# siedle-switch.net
KiCad netlist of a schematic drawn in EAGLE
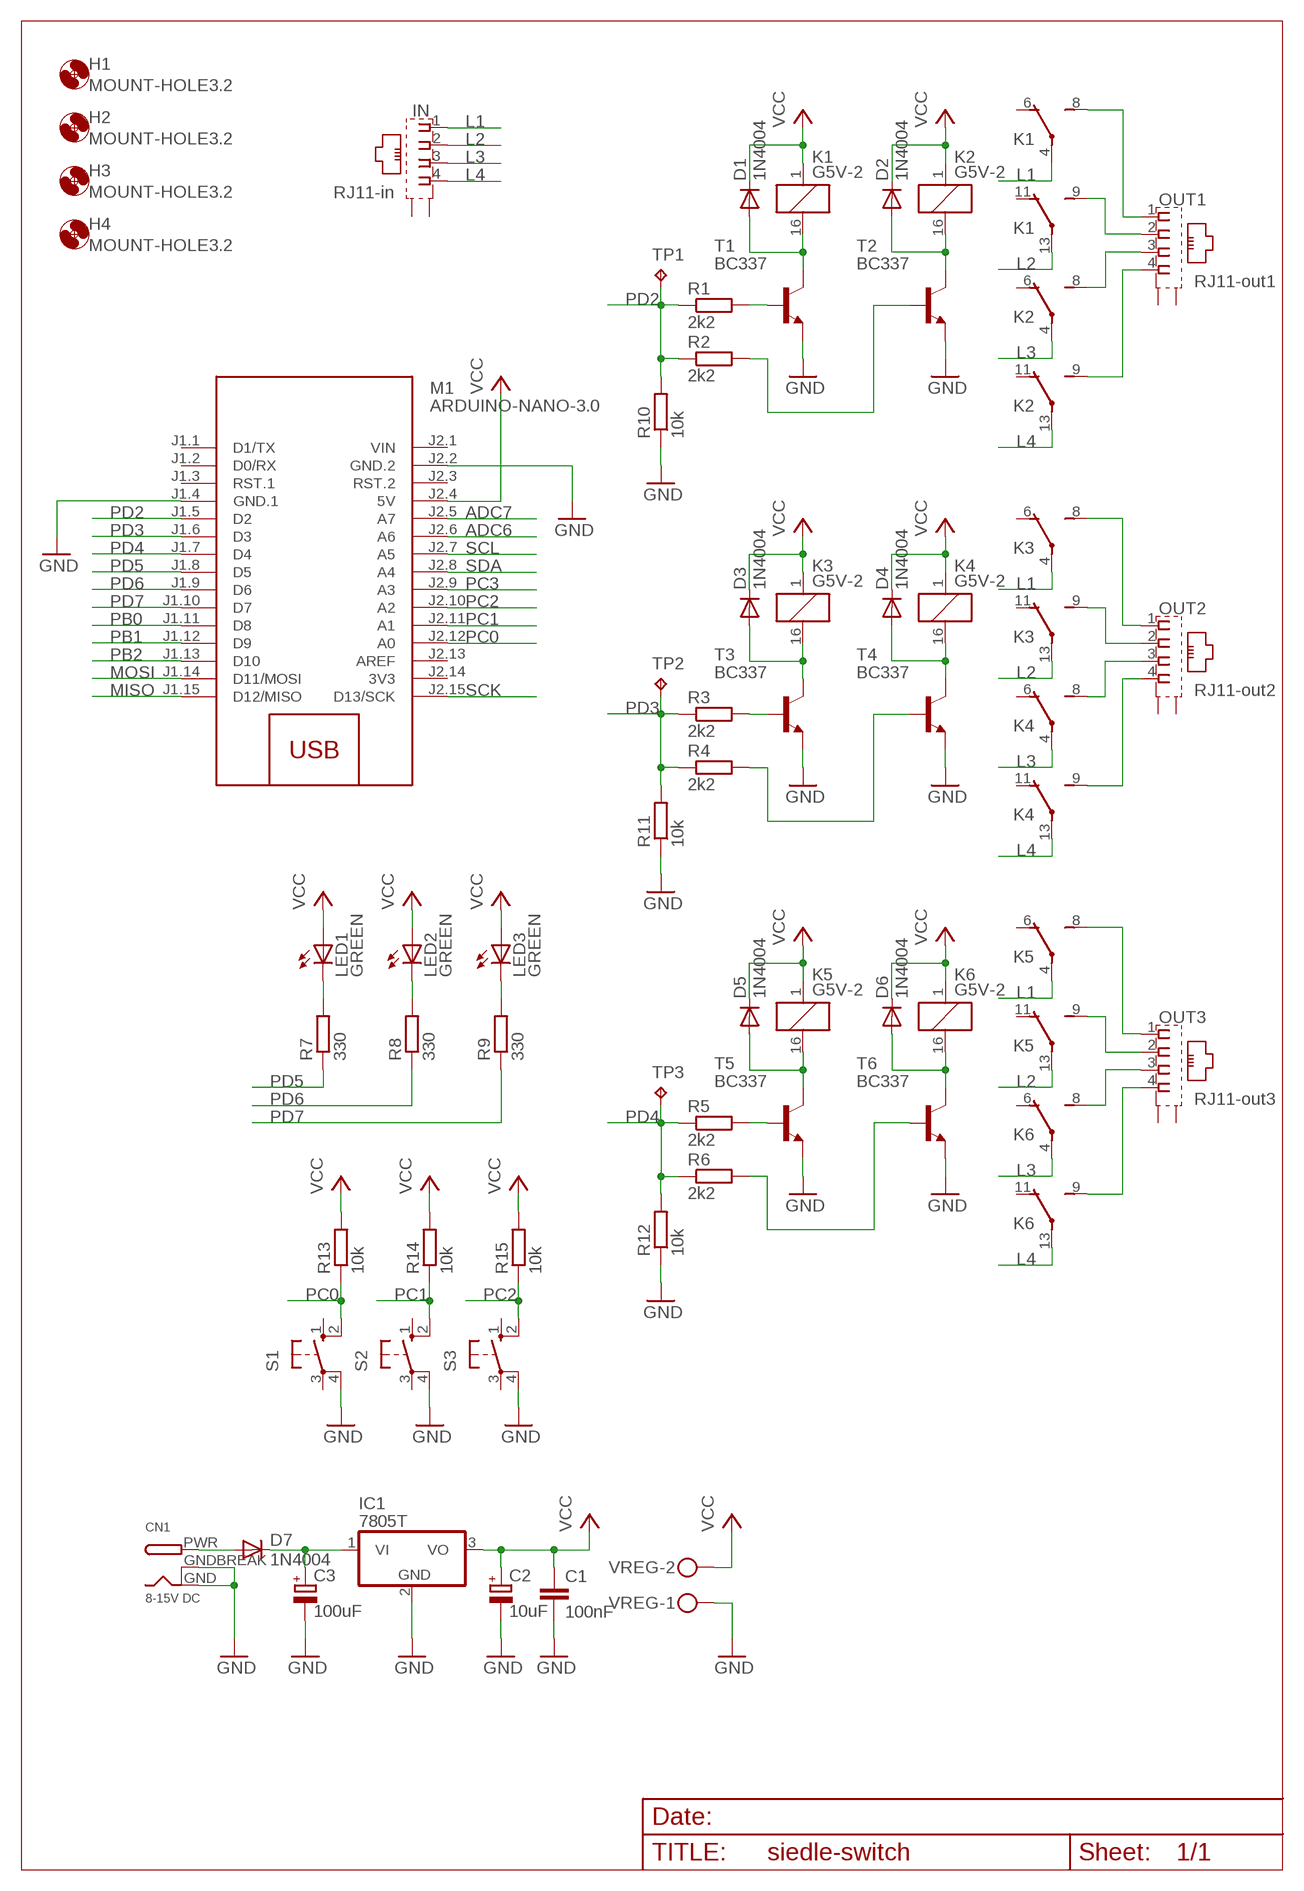
[diagram p0: schematic, sheet 1]

(export (version "E")
  (design (tool "Eeschema 10.0.6"))
  (components
    (comp (ref "C1")
      (value "100nF")
      (footprint "eagle-import:C1206")
      (libsource (lib "eagle-import") (part "C-EUC1206"))
    )
    (comp (ref "C2")
      (value "10uF")
      (footprint "eagle-import:E2,5-5")
      (libsource (lib "eagle-import") (part "CPOL-EUE2.5-5"))
    )
    (comp (ref "C3")
      (value "100uF")
      (footprint "eagle-import:E3,5-8")
      (libsource (lib "eagle-import") (part "CPOL-EUE3.5-8"))
    )
    (comp (ref "CN1")
      (value "8-15V DC")
      (footprint "eagle-import:DCJACK_2MM_PTH")
      (libsource (lib "eagle-import") (part "DCBARRELPTH"))
    )
    (comp (ref "D1")
      (value "1N4004")
      (footprint "eagle-import:DO41-10")
      (libsource (lib "eagle-import") (part "1N4004"))
    )
    (comp (ref "D2")
      (value "1N4004")
      (footprint "eagle-import:DO41-10")
      (libsource (lib "eagle-import") (part "1N4004"))
    )
    (comp (ref "D3")
      (value "1N4004")
      (footprint "eagle-import:DO41-10")
      (libsource (lib "eagle-import") (part "1N4004"))
    )
    (comp (ref "D4")
      (value "1N4004")
      (footprint "eagle-import:DO41-10")
      (libsource (lib "eagle-import") (part "1N4004"))
    )
    (comp (ref "D5")
      (value "1N4004")
      (footprint "eagle-import:DO41-10")
      (libsource (lib "eagle-import") (part "1N4004"))
    )
    (comp (ref "D6")
      (value "1N4004")
      (footprint "eagle-import:DO41-10")
      (libsource (lib "eagle-import") (part "1N4004"))
    )
    (comp (ref "D7")
      (value "1N4004")
      (footprint "eagle-import:DO41-10")
      (libsource (lib "eagle-import") (part "1N4004"))
    )
    (comp (ref "H1")
      (value "MOUNT-HOLE3.2")
      (footprint "eagle-import:3,2")
      (libsource (lib "eagle-import") (part "MOUNT-HOLE3.2"))
    )
    (comp (ref "H2")
      (value "MOUNT-HOLE3.2")
      (footprint "eagle-import:3,2")
      (libsource (lib "eagle-import") (part "MOUNT-HOLE3.2"))
    )
    (comp (ref "H3")
      (value "MOUNT-HOLE3.2")
      (footprint "eagle-import:3,2")
      (libsource (lib "eagle-import") (part "MOUNT-HOLE3.2"))
    )
    (comp (ref "H4")
      (value "MOUNT-HOLE3.2")
      (footprint "eagle-import:3,2")
      (libsource (lib "eagle-import") (part "MOUNT-HOLE3.2"))
    )
    (comp (ref "IC1")
      (value "7805T")
      (footprint "eagle-import:TO220H")
      (libsource (lib "eagle-import") (part "78T05"))
    )
    (comp (ref "IN")
      (value "RJ11-in")
      (footprint "eagle-import:XRJK-S-01-6-4-0-9M2")
      (libsource (lib "eagle-import") (part "XRJK4-0-9M2-S-01-6-"))
    )
    (comp (ref "K1")
      (value "G5V-2")
      (footprint "eagle-import:G5V-2")
      (fields (field (name "MPN") "G5V-2 5DC"))
      (libsource (lib "eagle-import") (part "G5V-2"))
    )
    (comp (ref "K2")
      (value "G5V-2")
      (footprint "eagle-import:G5V-2")
      (fields (field (name "MPN") "G5V-2 5DC"))
      (libsource (lib "eagle-import") (part "G5V-2"))
    )
    (comp (ref "K3")
      (value "G5V-2")
      (footprint "eagle-import:G5V-2")
      (fields (field (name "MPN") "G5V-2 5DC"))
      (libsource (lib "eagle-import") (part "G5V-2"))
    )
    (comp (ref "K4")
      (value "G5V-2")
      (footprint "eagle-import:G5V-2")
      (fields (field (name "MPN") "G5V-2 5DC"))
      (libsource (lib "eagle-import") (part "G5V-2"))
    )
    (comp (ref "K5")
      (value "G5V-2")
      (footprint "eagle-import:G5V-2")
      (fields (field (name "MPN") "G5V-2 5DC"))
      (libsource (lib "eagle-import") (part "G5V-2"))
    )
    (comp (ref "K6")
      (value "G5V-2")
      (footprint "eagle-import:G5V-2")
      (fields (field (name "MPN") "G5V-2 5DC"))
      (libsource (lib "eagle-import") (part "G5V-2"))
    )
    (comp (ref "LED1")
      (value "GREEN")
      (footprint "eagle-import:LED3MM")
      (libsource (lib "eagle-import") (part "LED3MM"))
    )
    (comp (ref "LED2")
      (value "GREEN")
      (footprint "eagle-import:LED3MM")
      (libsource (lib "eagle-import") (part "LED3MM"))
    )
    (comp (ref "LED3")
      (value "GREEN")
      (footprint "eagle-import:LED3MM")
      (libsource (lib "eagle-import") (part "LED3MM"))
    )
    (comp (ref "M1")
      (value "ARDUINO-NANO-3.0")
      (footprint "eagle-import:ARDUINO-NANO-3.0")
      (libsource (lib "eagle-import") (part "ARDUINO-NANO-3.0"))
    )
    (comp (ref "OUT1")
      (value "RJ11-out1")
      (footprint "eagle-import:XRJK-S-01-6-4-0-9M2")
      (libsource (lib "eagle-import") (part "XRJK4-0-9M2-S-01-6-"))
    )
    (comp (ref "OUT2")
      (value "RJ11-out2")
      (footprint "eagle-import:XRJK-S-01-6-4-0-9M2")
      (libsource (lib "eagle-import") (part "XRJK4-0-9M2-S-01-6-"))
    )
    (comp (ref "OUT3")
      (value "RJ11-out3")
      (footprint "eagle-import:XRJK-S-01-6-4-0-9M2")
      (libsource (lib "eagle-import") (part "XRJK4-0-9M2-S-01-6-"))
    )
    (comp (ref "R1")
      (value "2k2")
      (footprint "eagle-import:0309_10")
      (libsource (lib "eagle-import") (part "R-EU_0309/10"))
    )
    (comp (ref "R2")
      (value "2k2")
      (footprint "eagle-import:0309_10")
      (libsource (lib "eagle-import") (part "R-EU_0309/10"))
    )
    (comp (ref "R3")
      (value "2k2")
      (footprint "eagle-import:0309_10")
      (libsource (lib "eagle-import") (part "R-EU_0309/10"))
    )
    (comp (ref "R4")
      (value "2k2")
      (footprint "eagle-import:0309_10")
      (libsource (lib "eagle-import") (part "R-EU_0309/10"))
    )
    (comp (ref "R5")
      (value "2k2")
      (footprint "eagle-import:0309_10")
      (libsource (lib "eagle-import") (part "R-EU_0309/10"))
    )
    (comp (ref "R6")
      (value "2k2")
      (footprint "eagle-import:0309_10")
      (libsource (lib "eagle-import") (part "R-EU_0309/10"))
    )
    (comp (ref "R7")
      (value "330")
      (footprint "eagle-import:0309_10")
      (libsource (lib "eagle-import") (part "R-EU_0309/10"))
    )
    (comp (ref "R8")
      (value "330")
      (footprint "eagle-import:0309_10")
      (libsource (lib "eagle-import") (part "R-EU_0309/10"))
    )
    (comp (ref "R9")
      (value "330")
      (footprint "eagle-import:0309_10")
      (libsource (lib "eagle-import") (part "R-EU_0309/10"))
    )
    (comp (ref "R10")
      (value "10k")
      (footprint "eagle-import:0309_10")
      (libsource (lib "eagle-import") (part "R-EU_0309/10"))
    )
    (comp (ref "R11")
      (value "10k")
      (footprint "eagle-import:0309_10")
      (libsource (lib "eagle-import") (part "R-EU_0309/10"))
    )
    (comp (ref "R12")
      (value "10k")
      (footprint "eagle-import:0309_10")
      (libsource (lib "eagle-import") (part "R-EU_0309/10"))
    )
    (comp (ref "R13")
      (value "10k")
      (footprint "eagle-import:0309_10")
      (libsource (lib "eagle-import") (part "R-EU_0309/10"))
    )
    (comp (ref "R14")
      (value "10k")
      (footprint "eagle-import:0309_10")
      (libsource (lib "eagle-import") (part "R-EU_0309/10"))
    )
    (comp (ref "R15")
      (value "10k")
      (footprint "eagle-import:0309_10")
      (libsource (lib "eagle-import") (part "R-EU_0309/10"))
    )
    (comp (ref "S1")
      (value "10-XX")
      (footprint "eagle-import:B3F-10XX")
      (fields (field (name "MPN") "B3F-1000"))
      (libsource (lib "eagle-import") (part "10-XX"))
    )
    (comp (ref "S2")
      (value "10-XX")
      (footprint "eagle-import:B3F-10XX")
      (fields (field (name "MPN") "B3F-1000"))
      (libsource (lib "eagle-import") (part "10-XX"))
    )
    (comp (ref "S3")
      (value "10-XX")
      (footprint "eagle-import:B3F-10XX")
      (fields (field (name "MPN") "B3F-1000"))
      (libsource (lib "eagle-import") (part "10-XX"))
    )
    (comp (ref "T1")
      (value "BC337")
      (footprint "eagle-import:TO92")
      (libsource (lib "eagle-import") (part "BC337"))
    )
    (comp (ref "T2")
      (value "BC337")
      (footprint "eagle-import:TO92")
      (libsource (lib "eagle-import") (part "BC337"))
    )
    (comp (ref "T3")
      (value "BC337")
      (footprint "eagle-import:TO92")
      (libsource (lib "eagle-import") (part "BC337"))
    )
    (comp (ref "T4")
      (value "BC337")
      (footprint "eagle-import:TO92")
      (libsource (lib "eagle-import") (part "BC337"))
    )
    (comp (ref "T5")
      (value "BC337")
      (footprint "eagle-import:TO92")
      (libsource (lib "eagle-import") (part "BC337"))
    )
    (comp (ref "T6")
      (value "BC337")
      (footprint "eagle-import:TO92")
      (libsource (lib "eagle-import") (part "BC337"))
    )
    (comp (ref "TP1")
      (value "TPPAD1-13")
      (footprint "eagle-import:P1-13")
      (libsource (lib "eagle-import") (part "TPPAD1-13"))
    )
    (comp (ref "TP2")
      (value "TPPAD1-13")
      (footprint "eagle-import:P1-13")
      (libsource (lib "eagle-import") (part "TPPAD1-13"))
    )
    (comp (ref "TP3")
      (value "TPPAD1-13")
      (footprint "eagle-import:P1-13")
      (libsource (lib "eagle-import") (part "TPPAD1-13"))
    )
    (comp (ref "VREG")
      (value "MKDSN1,5/2-5,08")
      (footprint "eagle-import:MKDSN1,5_2-5,08")
      (fields (field (name "MPN") "MKDSN 1,5/2-5.08"))
      (libsource (lib "eagle-import") (part "MKDSN1,5/2-5,08"))
    )
  )
  (nets
    (net (code "1") (name "/3V3") (class "Default")
      (node (ref "M1") (pin "J2.14") (pinfunction "3V3_J2.14") (pintype "power_in"))
    )
    (net (code "2") (name "/ADC6") (class "Default")
      (node (ref "M1") (pin "J2.6") (pinfunction "A6_J2.6") (pintype "bidirectional"))
    )
    (net (code "3") (name "/ADC7") (class "Default")
      (node (ref "M1") (pin "J2.5") (pinfunction "A7_J2.5") (pintype "bidirectional"))
    )
    (net (code "4") (name "/L1") (class "Default")
      (node (ref "IN") (pin "1") (pinfunction "1_1") (pintype "passive"))
      (node (ref "K1") (pin "4") (pinfunction "P_4") (pintype "passive"))
      (node (ref "K3") (pin "4") (pinfunction "P_4") (pintype "passive"))
      (node (ref "K5") (pin "4") (pinfunction "P_4") (pintype "passive"))
    )
    (net (code "5") (name "/L2") (class "Default")
      (node (ref "IN") (pin "2") (pinfunction "2_2") (pintype "passive"))
      (node (ref "K1") (pin "13") (pinfunction "P_13") (pintype "passive"))
      (node (ref "K3") (pin "13") (pinfunction "P_13") (pintype "passive"))
      (node (ref "K5") (pin "13") (pinfunction "P_13") (pintype "passive"))
    )
    (net (code "6") (name "/L3") (class "Default")
      (node (ref "IN") (pin "3") (pinfunction "3_3") (pintype "passive"))
      (node (ref "K2") (pin "4") (pinfunction "P_4") (pintype "passive"))
      (node (ref "K4") (pin "4") (pinfunction "P_4") (pintype "passive"))
      (node (ref "K6") (pin "4") (pinfunction "P_4") (pintype "passive"))
    )
    (net (code "7") (name "/L4") (class "Default")
      (node (ref "IN") (pin "4") (pinfunction "4_4") (pintype "passive"))
      (node (ref "K2") (pin "13") (pinfunction "P_13") (pintype "passive"))
      (node (ref "K4") (pin "13") (pinfunction "P_13") (pintype "passive"))
      (node (ref "K6") (pin "13") (pinfunction "P_13") (pintype "passive"))
    )
    (net (code "8") (name "/MISO") (class "Default")
      (node (ref "M1") (pin "J1.15") (pinfunction "D12/MISO_J1.15") (pintype "bidirectional"))
    )
    (net (code "9") (name "/MOSI") (class "Default")
      (node (ref "M1") (pin "J1.14") (pinfunction "D11/MOSI_J1.14") (pintype "bidirectional"))
    )
    (net (code "10") (name "/PB0") (class "Default")
      (node (ref "M1") (pin "J1.11") (pinfunction "D8_J1.11") (pintype "bidirectional"))
    )
    (net (code "11") (name "/PB1") (class "Default")
      (node (ref "M1") (pin "J1.12") (pinfunction "D9_J1.12") (pintype "bidirectional"))
    )
    (net (code "12") (name "/PB2") (class "Default")
      (node (ref "M1") (pin "J1.13") (pinfunction "D10_J1.13") (pintype "bidirectional"))
    )
    (net (code "13") (name "/PC0") (class "Default")
      (node (ref "M1") (pin "J2.12") (pinfunction "A0_J2.12") (pintype "bidirectional"))
      (node (ref "R13") (pin "1") (pinfunction "1_1") (pintype "passive"))
      (node (ref "S1") (pin "2") (pinfunction "S1_2") (pintype "passive"))
    )
    (net (code "14") (name "/PC1") (class "Default")
      (node (ref "M1") (pin "J2.11") (pinfunction "A1_J2.11") (pintype "bidirectional"))
      (node (ref "R14") (pin "1") (pinfunction "1_1") (pintype "passive"))
      (node (ref "S2") (pin "2") (pinfunction "S1_2") (pintype "passive"))
    )
    (net (code "15") (name "/PC2") (class "Default")
      (node (ref "M1") (pin "J2.10") (pinfunction "A2_J2.10") (pintype "bidirectional"))
      (node (ref "R15") (pin "1") (pinfunction "1_1") (pintype "passive"))
      (node (ref "S3") (pin "2") (pinfunction "S1_2") (pintype "passive"))
    )
    (net (code "16") (name "/PC3") (class "Default")
      (node (ref "M1") (pin "J2.9") (pinfunction "A3_J2.9") (pintype "bidirectional"))
    )
    (net (code "17") (name "/PD2") (class "Default")
      (node (ref "M1") (pin "J1.5") (pinfunction "D2_J1.5") (pintype "bidirectional"))
      (node (ref "R1") (pin "1") (pinfunction "1_1") (pintype "passive"))
      (node (ref "R10") (pin "2") (pinfunction "2_2") (pintype "passive"))
      (node (ref "R2") (pin "1") (pinfunction "1_1") (pintype "passive"))
      (node (ref "TP1") (pin "TP") (pinfunction "TP_TP") (pintype "input"))
    )
    (net (code "18") (name "/PD3") (class "Default")
      (node (ref "M1") (pin "J1.6") (pinfunction "D3_J1.6") (pintype "bidirectional"))
      (node (ref "R11") (pin "2") (pinfunction "2_2") (pintype "passive"))
      (node (ref "R3") (pin "1") (pinfunction "1_1") (pintype "passive"))
      (node (ref "R4") (pin "1") (pinfunction "1_1") (pintype "passive"))
      (node (ref "TP2") (pin "TP") (pinfunction "TP_TP") (pintype "input"))
    )
    (net (code "19") (name "/PD4") (class "Default")
      (node (ref "M1") (pin "J1.7") (pinfunction "D4_J1.7") (pintype "bidirectional"))
      (node (ref "R12") (pin "2") (pinfunction "2_2") (pintype "passive"))
      (node (ref "R5") (pin "1") (pinfunction "1_1") (pintype "passive"))
      (node (ref "R6") (pin "1") (pinfunction "1_1") (pintype "passive"))
      (node (ref "TP3") (pin "TP") (pinfunction "TP_TP") (pintype "input"))
    )
    (net (code "20") (name "/PD5") (class "Default")
      (node (ref "M1") (pin "J1.8") (pinfunction "D5_J1.8") (pintype "bidirectional"))
      (node (ref "R7") (pin "1") (pinfunction "1_1") (pintype "passive"))
    )
    (net (code "21") (name "/PD6") (class "Default")
      (node (ref "M1") (pin "J1.9") (pinfunction "D6_J1.9") (pintype "bidirectional"))
      (node (ref "R8") (pin "1") (pinfunction "1_1") (pintype "passive"))
    )
    (net (code "22") (name "/PD7") (class "Default")
      (node (ref "M1") (pin "J1.10") (pinfunction "D7_J1.10") (pintype "bidirectional"))
      (node (ref "R9") (pin "1") (pinfunction "1_1") (pintype "passive"))
    )
    (net (code "23") (name "/SCK") (class "Default")
      (node (ref "M1") (pin "J2.15") (pinfunction "D13/SCK_J2.15") (pintype "bidirectional"))
    )
    (net (code "24") (name "/SCL") (class "Default")
      (node (ref "M1") (pin "J2.7") (pinfunction "A5_J2.7") (pintype "bidirectional"))
    )
    (net (code "25") (name "/SDA") (class "Default")
      (node (ref "M1") (pin "J2.8") (pinfunction "A4_J2.8") (pintype "bidirectional"))
    )
    (net (code "26") (name "/VIN") (class "Default")
      (node (ref "M1") (pin "J2.1") (pinfunction "VIN_J2.1") (pintype "power_in"))
    )
    (net (code "27") (name "GND") (class "Default")
      (node (ref "C1") (pin "2") (pinfunction "2_2") (pintype "passive"))
      (node (ref "C2") (pin "-") (pinfunction "-_-") (pintype "passive"))
      (node (ref "C3") (pin "-") (pinfunction "-_-") (pintype "passive"))
      (node (ref "CN1") (pin "GND") (pinfunction "GND_GND") (pintype "power_in"))
      (node (ref "CN1") (pin "GNDBREAK") (pinfunction "GNDBREAK_GNDBREAK") (pintype "power_in"))
      (node (ref "IC1") (pin "2") (pinfunction "GND_2") (pintype "passive"))
      (node (ref "M1") (pin "J1.4") (pinfunction "GND.1_J1.4") (pintype "power_in"))
      (node (ref "M1") (pin "J2.2") (pinfunction "GND.2_J2.2") (pintype "power_in"))
      (node (ref "R10") (pin "1") (pinfunction "1_1") (pintype "passive"))
      (node (ref "R11") (pin "1") (pinfunction "1_1") (pintype "passive"))
      (node (ref "R12") (pin "1") (pinfunction "1_1") (pintype "passive"))
      (node (ref "S1") (pin "4") (pinfunction "P1_4") (pintype "passive"))
      (node (ref "S2") (pin "4") (pinfunction "P1_4") (pintype "passive"))
      (node (ref "S3") (pin "4") (pinfunction "P1_4") (pintype "passive"))
      (node (ref "T1") (pin "1") (pinfunction "E_1") (pintype "passive"))
      (node (ref "T2") (pin "1") (pinfunction "E_1") (pintype "passive"))
      (node (ref "T3") (pin "1") (pinfunction "E_1") (pintype "passive"))
      (node (ref "T4") (pin "1") (pinfunction "E_1") (pintype "passive"))
      (node (ref "T5") (pin "1") (pinfunction "E_1") (pintype "passive"))
      (node (ref "T6") (pin "1") (pinfunction "E_1") (pintype "passive"))
      (node (ref "VREG") (pin "1") (pinfunction "KL_1") (pintype "passive"))
    )
    (net (code "28") (name "Net-(CN1-PadPWR)") (class "Default")
      (node (ref "CN1") (pin "PWR") (pinfunction "PWR_PWR") (pintype "power_in"))
      (node (ref "D7") (pin "A") (pinfunction "A_A") (pintype "passive"))
    )
    (net (code "29") (name "Net-(IC1-VI)") (class "Default")
      (node (ref "C3") (pin "+") (pinfunction "+_+") (pintype "passive"))
      (node (ref "D7") (pin "C") (pinfunction "C_C") (pintype "passive"))
      (node (ref "IC1") (pin "1") (pinfunction "VI_1") (pintype "input"))
    )
    (net (code "30") (name "Net-(K1A-S)") (class "Default")
      (node (ref "K1") (pin "8") (pinfunction "S_8") (pintype "passive"))
      (node (ref "OUT1") (pin "1") (pinfunction "1_1") (pintype "passive"))
    )
    (net (code "31") (name "Net-(K1B-S)") (class "Default")
      (node (ref "K1") (pin "9") (pinfunction "S_9") (pintype "passive"))
      (node (ref "OUT1") (pin "2") (pinfunction "2_2") (pintype "passive"))
    )
    (net (code "32") (name "Net-(K1C-2)") (class "Default")
      (node (ref "D1") (pin "A") (pinfunction "A_A") (pintype "passive"))
      (node (ref "K1") (pin "16") (pinfunction "2_16") (pintype "passive"))
      (node (ref "T1") (pin "3") (pinfunction "C_3") (pintype "passive"))
    )
    (net (code "33") (name "Net-(K2A-S)") (class "Default")
      (node (ref "K2") (pin "8") (pinfunction "S_8") (pintype "passive"))
      (node (ref "OUT1") (pin "3") (pinfunction "3_3") (pintype "passive"))
    )
    (net (code "34") (name "Net-(K2B-S)") (class "Default")
      (node (ref "K2") (pin "9") (pinfunction "S_9") (pintype "passive"))
      (node (ref "OUT1") (pin "4") (pinfunction "4_4") (pintype "passive"))
    )
    (net (code "35") (name "Net-(K2C-2)") (class "Default")
      (node (ref "D2") (pin "A") (pinfunction "A_A") (pintype "passive"))
      (node (ref "K2") (pin "16") (pinfunction "2_16") (pintype "passive"))
      (node (ref "T2") (pin "3") (pinfunction "C_3") (pintype "passive"))
    )
    (net (code "36") (name "Net-(K3A-S)") (class "Default")
      (node (ref "K3") (pin "8") (pinfunction "S_8") (pintype "passive"))
      (node (ref "OUT2") (pin "1") (pinfunction "1_1") (pintype "passive"))
    )
    (net (code "37") (name "Net-(K3B-S)") (class "Default")
      (node (ref "K3") (pin "9") (pinfunction "S_9") (pintype "passive"))
      (node (ref "OUT2") (pin "2") (pinfunction "2_2") (pintype "passive"))
    )
    (net (code "38") (name "Net-(K3C-2)") (class "Default")
      (node (ref "D3") (pin "A") (pinfunction "A_A") (pintype "passive"))
      (node (ref "K3") (pin "16") (pinfunction "2_16") (pintype "passive"))
      (node (ref "T3") (pin "3") (pinfunction "C_3") (pintype "passive"))
    )
    (net (code "39") (name "Net-(K4A-S)") (class "Default")
      (node (ref "K4") (pin "8") (pinfunction "S_8") (pintype "passive"))
      (node (ref "OUT2") (pin "3") (pinfunction "3_3") (pintype "passive"))
    )
    (net (code "40") (name "Net-(K4B-S)") (class "Default")
      (node (ref "K4") (pin "9") (pinfunction "S_9") (pintype "passive"))
      (node (ref "OUT2") (pin "4") (pinfunction "4_4") (pintype "passive"))
    )
    (net (code "41") (name "Net-(K4C-2)") (class "Default")
      (node (ref "D4") (pin "A") (pinfunction "A_A") (pintype "passive"))
      (node (ref "K4") (pin "16") (pinfunction "2_16") (pintype "passive"))
      (node (ref "T4") (pin "3") (pinfunction "C_3") (pintype "passive"))
    )
    (net (code "42") (name "Net-(K5A-S)") (class "Default")
      (node (ref "K5") (pin "8") (pinfunction "S_8") (pintype "passive"))
      (node (ref "OUT3") (pin "1") (pinfunction "1_1") (pintype "passive"))
    )
    (net (code "43") (name "Net-(K5B-S)") (class "Default")
      (node (ref "K5") (pin "9") (pinfunction "S_9") (pintype "passive"))
      (node (ref "OUT3") (pin "2") (pinfunction "2_2") (pintype "passive"))
    )
    (net (code "44") (name "Net-(K5C-2)") (class "Default")
      (node (ref "D5") (pin "A") (pinfunction "A_A") (pintype "passive"))
      (node (ref "K5") (pin "16") (pinfunction "2_16") (pintype "passive"))
      (node (ref "T5") (pin "3") (pinfunction "C_3") (pintype "passive"))
    )
    (net (code "45") (name "Net-(K6A-S)") (class "Default")
      (node (ref "K6") (pin "8") (pinfunction "S_8") (pintype "passive"))
      (node (ref "OUT3") (pin "3") (pinfunction "3_3") (pintype "passive"))
    )
    (net (code "46") (name "Net-(K6B-S)") (class "Default")
      (node (ref "K6") (pin "9") (pinfunction "S_9") (pintype "passive"))
      (node (ref "OUT3") (pin "4") (pinfunction "4_4") (pintype "passive"))
    )
    (net (code "47") (name "Net-(K6C-2)") (class "Default")
      (node (ref "D6") (pin "A") (pinfunction "A_A") (pintype "passive"))
      (node (ref "K6") (pin "16") (pinfunction "2_16") (pintype "passive"))
      (node (ref "T6") (pin "3") (pinfunction "C_3") (pintype "passive"))
    )
    (net (code "48") (name "Net-(LED1-C)") (class "Default")
      (node (ref "LED1") (pin "K") (pinfunction "C_K") (pintype "passive"))
      (node (ref "R7") (pin "2") (pinfunction "2_2") (pintype "passive"))
    )
    (net (code "49") (name "Net-(LED2-C)") (class "Default")
      (node (ref "LED2") (pin "K") (pinfunction "C_K") (pintype "passive"))
      (node (ref "R8") (pin "2") (pinfunction "2_2") (pintype "passive"))
    )
    (net (code "50") (name "Net-(LED3-C)") (class "Default")
      (node (ref "LED3") (pin "K") (pinfunction "C_K") (pintype "passive"))
      (node (ref "R9") (pin "2") (pinfunction "2_2") (pintype "passive"))
    )
    (net (code "51") (name "Net-(T1-B)") (class "Default")
      (node (ref "R1") (pin "2") (pinfunction "2_2") (pintype "passive"))
      (node (ref "T1") (pin "2") (pinfunction "B_2") (pintype "passive"))
    )
    (net (code "52") (name "Net-(T2-B)") (class "Default")
      (node (ref "R2") (pin "2") (pinfunction "2_2") (pintype "passive"))
      (node (ref "T2") (pin "2") (pinfunction "B_2") (pintype "passive"))
    )
    (net (code "53") (name "Net-(T3-B)") (class "Default")
      (node (ref "R3") (pin "2") (pinfunction "2_2") (pintype "passive"))
      (node (ref "T3") (pin "2") (pinfunction "B_2") (pintype "passive"))
    )
    (net (code "54") (name "Net-(T4-B)") (class "Default")
      (node (ref "R4") (pin "2") (pinfunction "2_2") (pintype "passive"))
      (node (ref "T4") (pin "2") (pinfunction "B_2") (pintype "passive"))
    )
    (net (code "55") (name "Net-(T5-B)") (class "Default")
      (node (ref "R5") (pin "2") (pinfunction "2_2") (pintype "passive"))
      (node (ref "T5") (pin "2") (pinfunction "B_2") (pintype "passive"))
    )
    (net (code "56") (name "Net-(T6-B)") (class "Default")
      (node (ref "R6") (pin "2") (pinfunction "2_2") (pintype "passive"))
      (node (ref "T6") (pin "2") (pinfunction "B_2") (pintype "passive"))
    )
    (net (code "57") (name "VCC") (class "Default")
      (node (ref "C1") (pin "1") (pinfunction "1_1") (pintype "passive"))
      (node (ref "C2") (pin "+") (pinfunction "+_+") (pintype "passive"))
      (node (ref "D1") (pin "C") (pinfunction "C_C") (pintype "passive"))
      (node (ref "D2") (pin "C") (pinfunction "C_C") (pintype "passive"))
      (node (ref "D3") (pin "C") (pinfunction "C_C") (pintype "passive"))
      (node (ref "D4") (pin "C") (pinfunction "C_C") (pintype "passive"))
      (node (ref "D5") (pin "C") (pinfunction "C_C") (pintype "passive"))
      (node (ref "D6") (pin "C") (pinfunction "C_C") (pintype "passive"))
      (node (ref "IC1") (pin "3") (pinfunction "VO_3") (pintype "passive"))
      (node (ref "K1") (pin "1") (pinfunction "1_1") (pintype "passive"))
      (node (ref "K2") (pin "1") (pinfunction "1_1") (pintype "passive"))
      (node (ref "K3") (pin "1") (pinfunction "1_1") (pintype "passive"))
      (node (ref "K4") (pin "1") (pinfunction "1_1") (pintype "passive"))
      (node (ref "K5") (pin "1") (pinfunction "1_1") (pintype "passive"))
      (node (ref "K6") (pin "1") (pinfunction "1_1") (pintype "passive"))
      (node (ref "LED1") (pin "A") (pinfunction "A_A") (pintype "passive"))
      (node (ref "LED2") (pin "A") (pinfunction "A_A") (pintype "passive"))
      (node (ref "LED3") (pin "A") (pinfunction "A_A") (pintype "passive"))
      (node (ref "M1") (pin "J2.4") (pinfunction "5V_J2.4") (pintype "power_in"))
      (node (ref "R13") (pin "2") (pinfunction "2_2") (pintype "passive"))
      (node (ref "R14") (pin "2") (pinfunction "2_2") (pintype "passive"))
      (node (ref "R15") (pin "2") (pinfunction "2_2") (pintype "passive"))
      (node (ref "VREG") (pin "2") (pinfunction "KL_2") (pintype "passive"))
    )
    (net (code "58") (name "unconnected-(IN-S-PadS1)") (class "Default")
      (node (ref "IN") (pin "S1") (pinfunction "S_S1") (pintype "passive"))
    )
    (net (code "59") (name "unconnected-(IN-S-PadS2)") (class "Default")
      (node (ref "IN") (pin "S2") (pinfunction "S_S2") (pintype "passive"))
    )
    (net (code "60") (name "unconnected-(K1A-O-Pad6)") (class "Default")
      (node (ref "K1") (pin "6") (pinfunction "O_6") (pintype "passive"))
    )
    (net (code "61") (name "unconnected-(K1B-O-Pad11)") (class "Default")
      (node (ref "K1") (pin "11") (pinfunction "O_11") (pintype "passive"))
    )
    (net (code "62") (name "unconnected-(K2A-O-Pad6)") (class "Default")
      (node (ref "K2") (pin "6") (pinfunction "O_6") (pintype "passive"))
    )
    (net (code "63") (name "unconnected-(K2B-O-Pad11)") (class "Default")
      (node (ref "K2") (pin "11") (pinfunction "O_11") (pintype "passive"))
    )
    (net (code "64") (name "unconnected-(K3A-O-Pad6)") (class "Default")
      (node (ref "K3") (pin "6") (pinfunction "O_6") (pintype "passive"))
    )
    (net (code "65") (name "unconnected-(K3B-O-Pad11)") (class "Default")
      (node (ref "K3") (pin "11") (pinfunction "O_11") (pintype "passive"))
    )
    (net (code "66") (name "unconnected-(K4A-O-Pad6)") (class "Default")
      (node (ref "K4") (pin "6") (pinfunction "O_6") (pintype "passive"))
    )
    (net (code "67") (name "unconnected-(K4B-O-Pad11)") (class "Default")
      (node (ref "K4") (pin "11") (pinfunction "O_11") (pintype "passive"))
    )
    (net (code "68") (name "unconnected-(K5A-O-Pad6)") (class "Default")
      (node (ref "K5") (pin "6") (pinfunction "O_6") (pintype "passive"))
    )
    (net (code "69") (name "unconnected-(K5B-O-Pad11)") (class "Default")
      (node (ref "K5") (pin "11") (pinfunction "O_11") (pintype "passive"))
    )
    (net (code "70") (name "unconnected-(K6A-O-Pad6)") (class "Default")
      (node (ref "K6") (pin "6") (pinfunction "O_6") (pintype "passive"))
    )
    (net (code "71") (name "unconnected-(K6B-O-Pad11)") (class "Default")
      (node (ref "K6") (pin "11") (pinfunction "O_11") (pintype "passive"))
    )
    (net (code "72") (name "unconnected-(M1-AREF-PadJ2.13)") (class "Default")
      (node (ref "M1") (pin "J2.13") (pinfunction "AREF_J2.13") (pintype "bidirectional"))
    )
    (net (code "73") (name "unconnected-(M1-D0{slash}RX-PadJ1.2)") (class "Default")
      (node (ref "M1") (pin "J1.2") (pinfunction "D0/RX_J1.2") (pintype "bidirectional"))
    )
    (net (code "74") (name "unconnected-(M1-D1{slash}TX-PadJ1.1)") (class "Default")
      (node (ref "M1") (pin "J1.1") (pinfunction "D1/TX_J1.1") (pintype "bidirectional"))
    )
    (net (code "75") (name "unconnected-(M1-RST.1-PadJ1.3)") (class "Default")
      (node (ref "M1") (pin "J1.3") (pinfunction "RST.1_J1.3") (pintype "bidirectional"))
    )
    (net (code "76") (name "unconnected-(M1-RST.2-PadJ2.3)") (class "Default")
      (node (ref "M1") (pin "J2.3") (pinfunction "RST.2_J2.3") (pintype "bidirectional"))
    )
    (net (code "77") (name "unconnected-(OUT1-S-PadS1)") (class "Default")
      (node (ref "OUT1") (pin "S1") (pinfunction "S_S1") (pintype "passive"))
    )
    (net (code "78") (name "unconnected-(OUT1-S-PadS2)") (class "Default")
      (node (ref "OUT1") (pin "S2") (pinfunction "S_S2") (pintype "passive"))
    )
    (net (code "79") (name "unconnected-(OUT2-S-PadS1)") (class "Default")
      (node (ref "OUT2") (pin "S1") (pinfunction "S_S1") (pintype "passive"))
    )
    (net (code "80") (name "unconnected-(OUT2-S-PadS2)") (class "Default")
      (node (ref "OUT2") (pin "S2") (pinfunction "S_S2") (pintype "passive"))
    )
    (net (code "81") (name "unconnected-(OUT3-S-PadS1)") (class "Default")
      (node (ref "OUT3") (pin "S1") (pinfunction "S_S1") (pintype "passive"))
    )
    (net (code "82") (name "unconnected-(OUT3-S-PadS2)") (class "Default")
      (node (ref "OUT3") (pin "S2") (pinfunction "S_S2") (pintype "passive"))
    )
    (net (code "83") (name "unconnected-(S1-P-Pad3)") (class "Default")
      (node (ref "S1") (pin "3") (pinfunction "P_3") (pintype "passive"))
    )
    (net (code "84") (name "unconnected-(S1-S-Pad1)") (class "Default")
      (node (ref "S1") (pin "1") (pinfunction "S_1") (pintype "passive"))
    )
    (net (code "85") (name "unconnected-(S2-P-Pad3)") (class "Default")
      (node (ref "S2") (pin "3") (pinfunction "P_3") (pintype "passive"))
    )
    (net (code "86") (name "unconnected-(S2-S-Pad1)") (class "Default")
      (node (ref "S2") (pin "1") (pinfunction "S_1") (pintype "passive"))
    )
    (net (code "87") (name "unconnected-(S3-P-Pad3)") (class "Default")
      (node (ref "S3") (pin "3") (pinfunction "P_3") (pintype "passive"))
    )
    (net (code "88") (name "unconnected-(S3-S-Pad1)") (class "Default")
      (node (ref "S3") (pin "1") (pinfunction "S_1") (pintype "passive"))
    )
  )
)
